# Sensor.net
KiCad netlist of a schematic drawn in Altium Designer
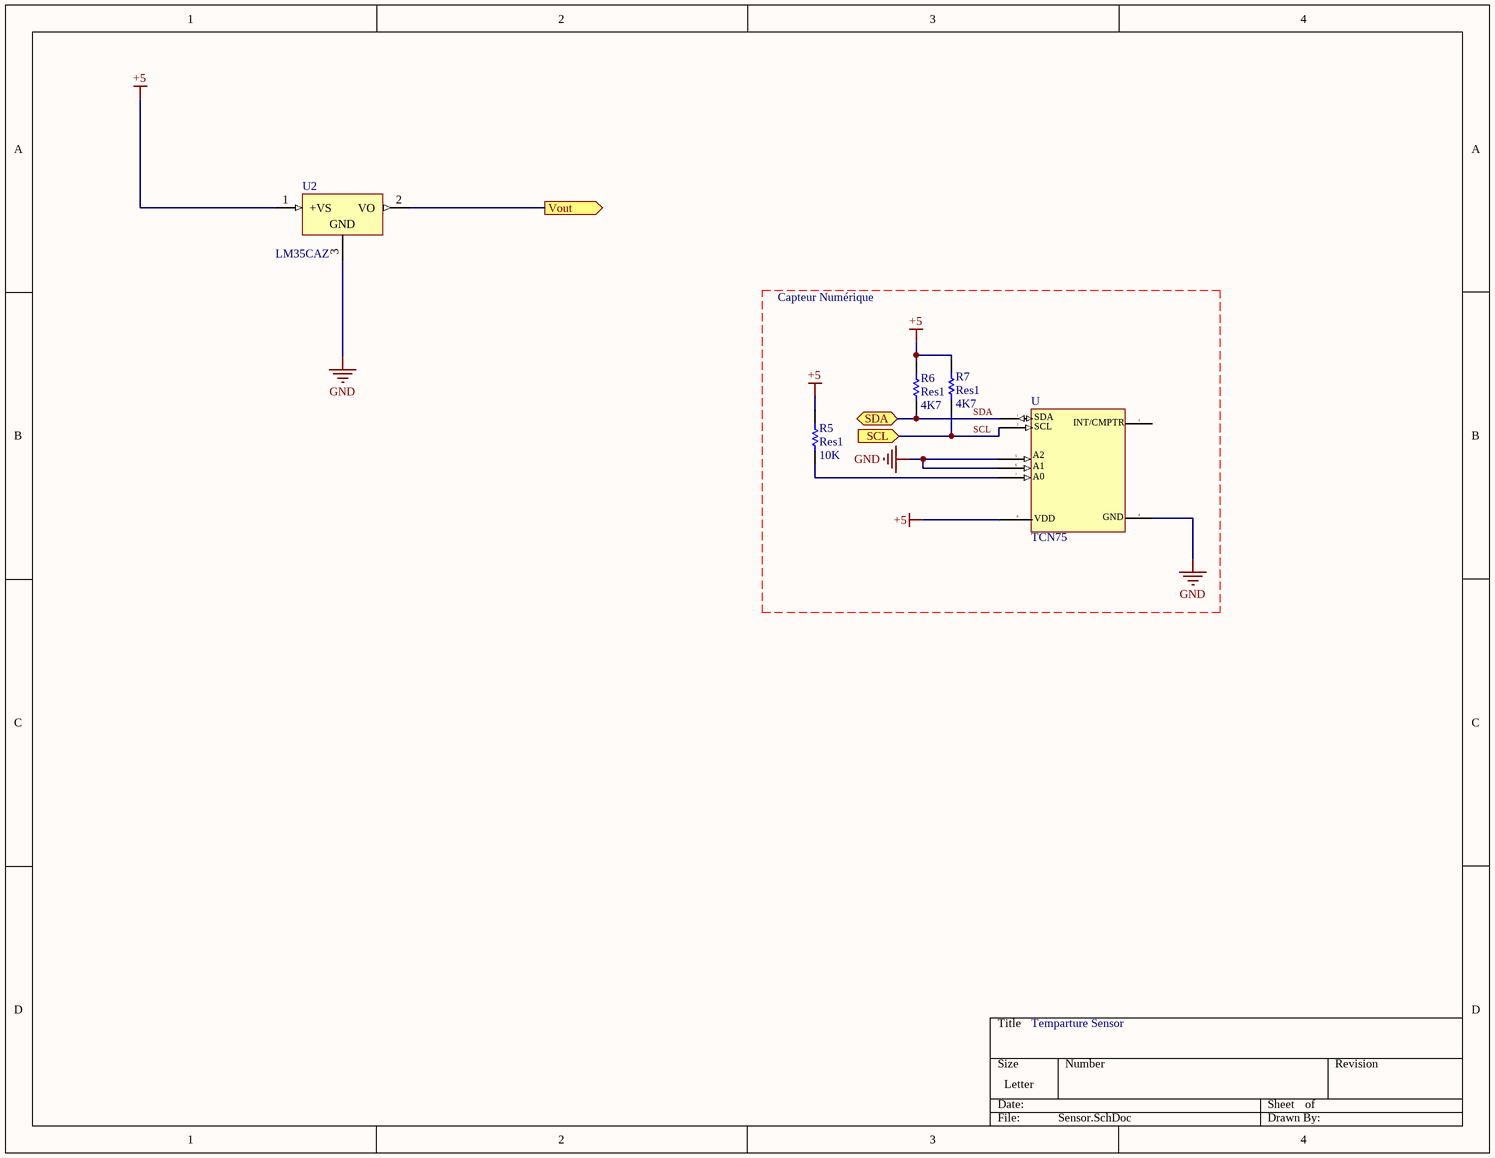
[diagram p0: Sensor.SchDoc]

(export (version "E")
  (design (tool "Eeschema 10.0.6"))
  (components
    (comp (ref "R5")
      (value "Res1")
      (footprint "AXIAL-0.3")
      (description "Resistor")
      (fields (field (name "ALTIUM_VALUE") "10K") (field (name "PUBLISHER") "Altium Limited"))
      (libsource (lib "Miscellaneous Devices") (part "Res1"))
    )
    (comp (ref "R6")
      (value "Res1")
      (footprint "AXIAL-0.3")
      (description "Resistor")
      (fields (field (name "ALTIUM_VALUE") "4K7") (field (name "PUBLISHER") "Altium Limited"))
      (libsource (lib "Miscellaneous Devices") (part "Res1"))
    )
    (comp (ref "R7")
      (value "Res1")
      (footprint "AXIAL-0.3")
      (description "Resistor")
      (fields (field (name "ALTIUM_VALUE") "4K7") (field (name "PUBLISHER") "Altium Limited"))
      (libsource (lib "Miscellaneous Devices") (part "Res1"))
    )
    (comp (ref "U") (value "TCN75") (footprint "SOIC127P600X175-8N") (libsource (lib "TP3") (part "TCN75")))
    (comp (ref "U2")
      (value "LM35CAZ")
      (footprint "Z03A")
      (description "Precision Centigrade Temperature Sensor, 3-pin TO-92")
      (fields
        (field (name "MANUFACTURER") "National Semiconductor")
        (field (name "PUBLISHER") "Altium Limited")
      )
      (libsource (lib "NSC Temperature Sensor") (part "LM35CAZ"))
    )
  )
  (nets
    (net (code "1") (name "+5") (class "Default")
      (node (ref "R5") (pin "2") (pinfunction "2_2") (pintype "passive"))
      (node (ref "R6") (pin "2") (pinfunction "2_2") (pintype "passive"))
      (node (ref "R7") (pin "2") (pinfunction "2_2") (pintype "passive"))
      (node (ref "U") (pin "8") (pintype "passive"))
      (node (ref "U2") (pin "1") (pinfunction "+VS_1") (pintype "input"))
    )
    (net (code "2") (name "/SCL") (class "Default")
      (node (ref "R7") (pin "1") (pinfunction "1_1") (pintype "passive"))
      (node (ref "U") (pin "2") (pintype "input"))
    )
    (net (code "3") (name "/SDA") (class "Default")
      (node (ref "R6") (pin "1") (pinfunction "1_1") (pintype "passive"))
      (node (ref "U") (pin "1") (pintype "bidirectional"))
    )
    (net (code "4") (name "/Vout") (class "Default")
      (node (ref "U2") (pin "2") (pinfunction "VO_2") (pintype "output"))
    )
    (net (code "5") (name "GND") (class "Default")
      (node (ref "U") (pin "4") (pintype "passive"))
      (node (ref "U") (pin "5") (pintype "input"))
      (node (ref "U") (pin "6") (pintype "input"))
      (node (ref "U2") (pin "3") (pinfunction "GND_3") (pintype "power_in"))
    )
    (net (code "6") (name "Net-(R5-Pad1)") (class "Default")
      (node (ref "R5") (pin "1") (pinfunction "1_1") (pintype "passive"))
      (node (ref "U") (pin "7") (pintype "input"))
    )
    (net (code "7") (name "unconnected-(U-Pad3)") (class "Default")
      (node (ref "U") (pin "3") (pintype "passive"))
    )
  )
)
